# Buttons.net
KiCad netlist of a schematic drawn in Altium Designer
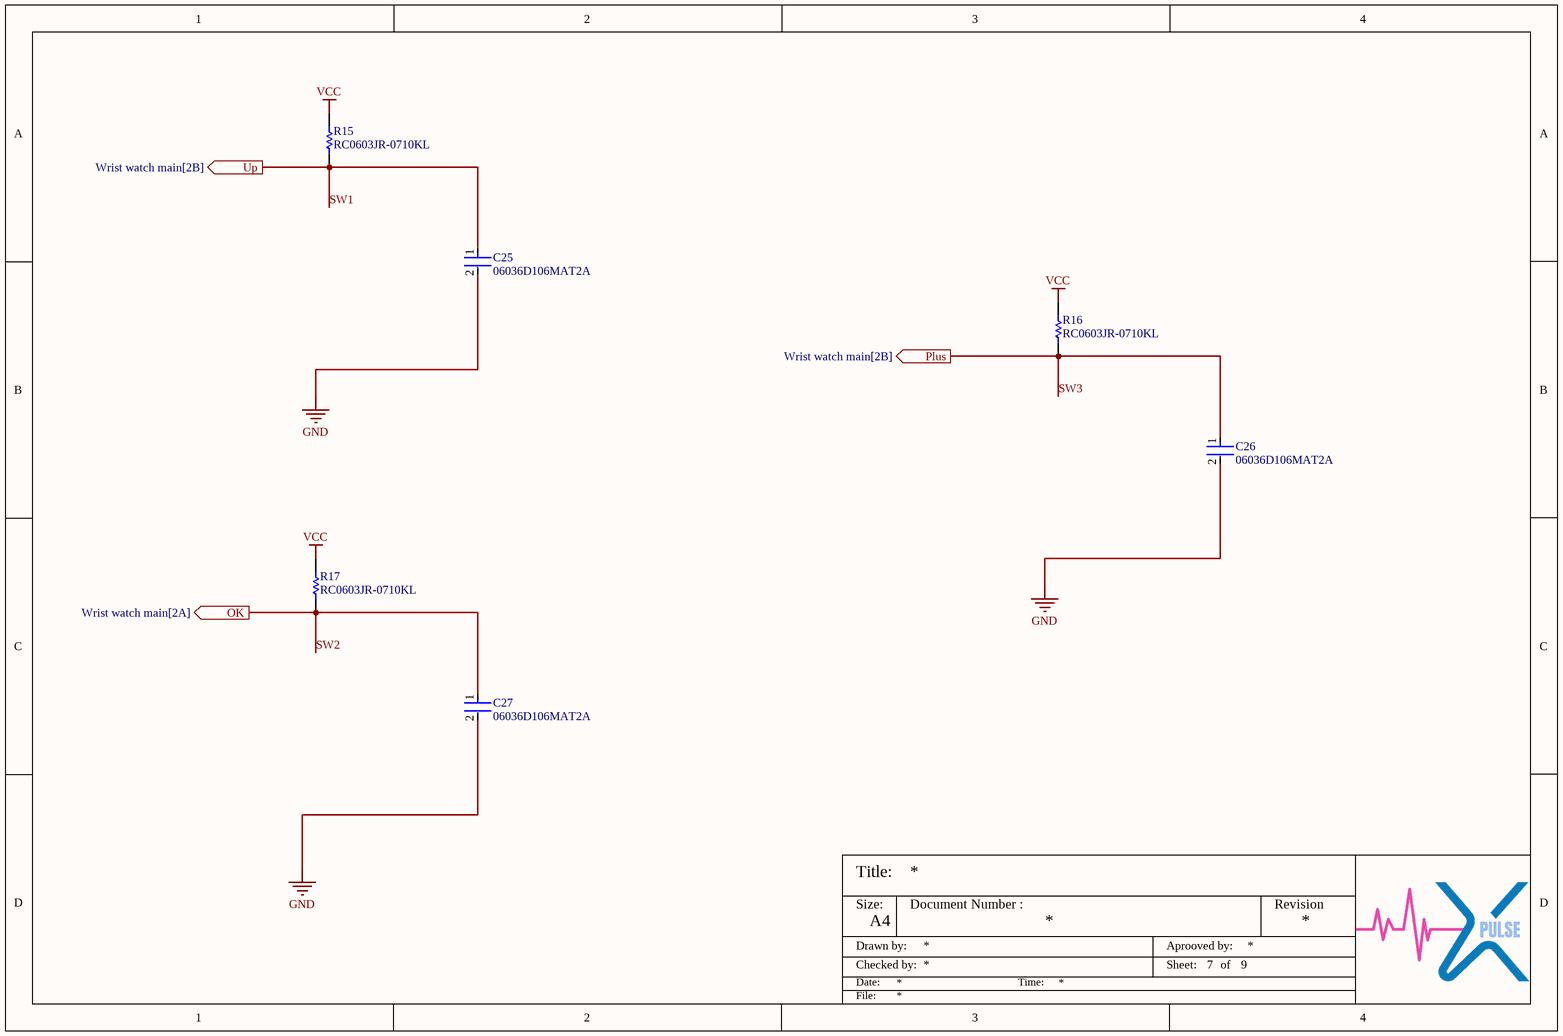
[diagram p0: Buttons.SchDoc]

(export (version "E")
  (design (tool "Eeschema 10.0.6"))
  (components
    (comp (ref "C25")
      (value "06036D106MAT2A")
      (footprint "FP-0603-L_1_6_0_15-W_0_81-IPC_B")
      (description "General Purpose Ceramic Capacitor, 0603, 10uF, 20%, X5R, 15%, 6.3V")
      (fields (field (name "TOLERANCE") "20%") (field (name "VOLTAGE") "6.3V"))
      (libsource (lib "Altium Content Vault") (part "02cd4be3c70576c341d710602a673aa"))
    )
    (comp (ref "C26")
      (value "06036D106MAT2A")
      (footprint "FP-0603-L_1_6_0_15-W_0_81-IPC_B")
      (description "General Purpose Ceramic Capacitor, 0603, 10uF, 20%, X5R, 15%, 6.3V")
      (fields (field (name "TOLERANCE") "20%") (field (name "VOLTAGE") "6.3V"))
      (libsource (lib "Altium Content Vault") (part "02cd4be3c70576c341d710602a673aa"))
    )
    (comp (ref "C27")
      (value "06036D106MAT2A")
      (footprint "FP-0603-L_1_6_0_15-W_0_81-IPC_B")
      (description "General Purpose Ceramic Capacitor, 0603, 10uF, 20%, X5R, 15%, 6.3V")
      (fields (field (name "TOLERANCE") "20%") (field (name "VOLTAGE") "6.3V"))
      (libsource (lib "Altium Content Vault") (part "02cd4be3c70576c341d710602a673aa"))
    )
    (comp (ref "R15")
      (value "RC0603JR-0710KL")
      (footprint "RESC1608X55X25ML10T15")
      (description "Resistor, 10 KOhm, +/- 5%, 100 mW, -55 to 155 degC, 0603 (1608 Metric), RoHS, Tape and Reel")
      (fields (field (name "MANUFACTURER") "Yageo") (field (name "TOLERANCE") "5%"))
      (libsource (lib "Altium Content Vault") (part "RES-2"))
    )
    (comp (ref "R16")
      (value "RC0603JR-0710KL")
      (footprint "RESC1608X55X25ML10T15")
      (description "Resistor, 10 KOhm, +/- 5%, 100 mW, -55 to 155 degC, 0603 (1608 Metric), RoHS, Tape and Reel")
      (fields (field (name "MANUFACTURER") "Yageo") (field (name "TOLERANCE") "5%"))
      (libsource (lib "Altium Content Vault") (part "RES-2"))
    )
    (comp (ref "R17")
      (value "RC0603JR-0710KL")
      (footprint "RESC1608X55X25ML10T15")
      (description "Resistor, 10 KOhm, +/- 5%, 100 mW, -55 to 155 degC, 0603 (1608 Metric), RoHS, Tape and Reel")
      (fields (field (name "MANUFACTURER") "Yageo") (field (name "TOLERANCE") "5%"))
      (libsource (lib "Altium Content Vault") (part "RES-2"))
    )
  )
  (nets
    (net (code "1") (name "/SW1") (class "Default")
      (node (ref "C25") (pin "1") (pinfunction "1_1") (pintype "passive"))
      (node (ref "R15") (pin "1") (pinfunction "1_1") (pintype "passive"))
    )
    (net (code "2") (name "/SW2") (class "Default")
      (node (ref "C27") (pin "1") (pinfunction "1_1") (pintype "passive"))
      (node (ref "R17") (pin "1") (pinfunction "1_1") (pintype "passive"))
    )
    (net (code "3") (name "/SW3") (class "Default")
      (node (ref "C26") (pin "1") (pinfunction "1_1") (pintype "passive"))
      (node (ref "R16") (pin "1") (pinfunction "1_1") (pintype "passive"))
    )
    (net (code "4") (name "GND") (class "Default")
      (node (ref "C25") (pin "2") (pinfunction "2_2") (pintype "passive"))
      (node (ref "C26") (pin "2") (pinfunction "2_2") (pintype "passive"))
      (node (ref "C27") (pin "2") (pinfunction "2_2") (pintype "passive"))
    )
    (net (code "5") (name "VCC") (class "Default")
      (node (ref "R15") (pin "2") (pinfunction "2_2") (pintype "passive"))
      (node (ref "R16") (pin "2") (pinfunction "2_2") (pintype "passive"))
      (node (ref "R17") (pin "2") (pinfunction "2_2") (pintype "passive"))
    )
  )
)
